# COOP4403.net
KiCad netlist of a schematic drawn in Altium Designer
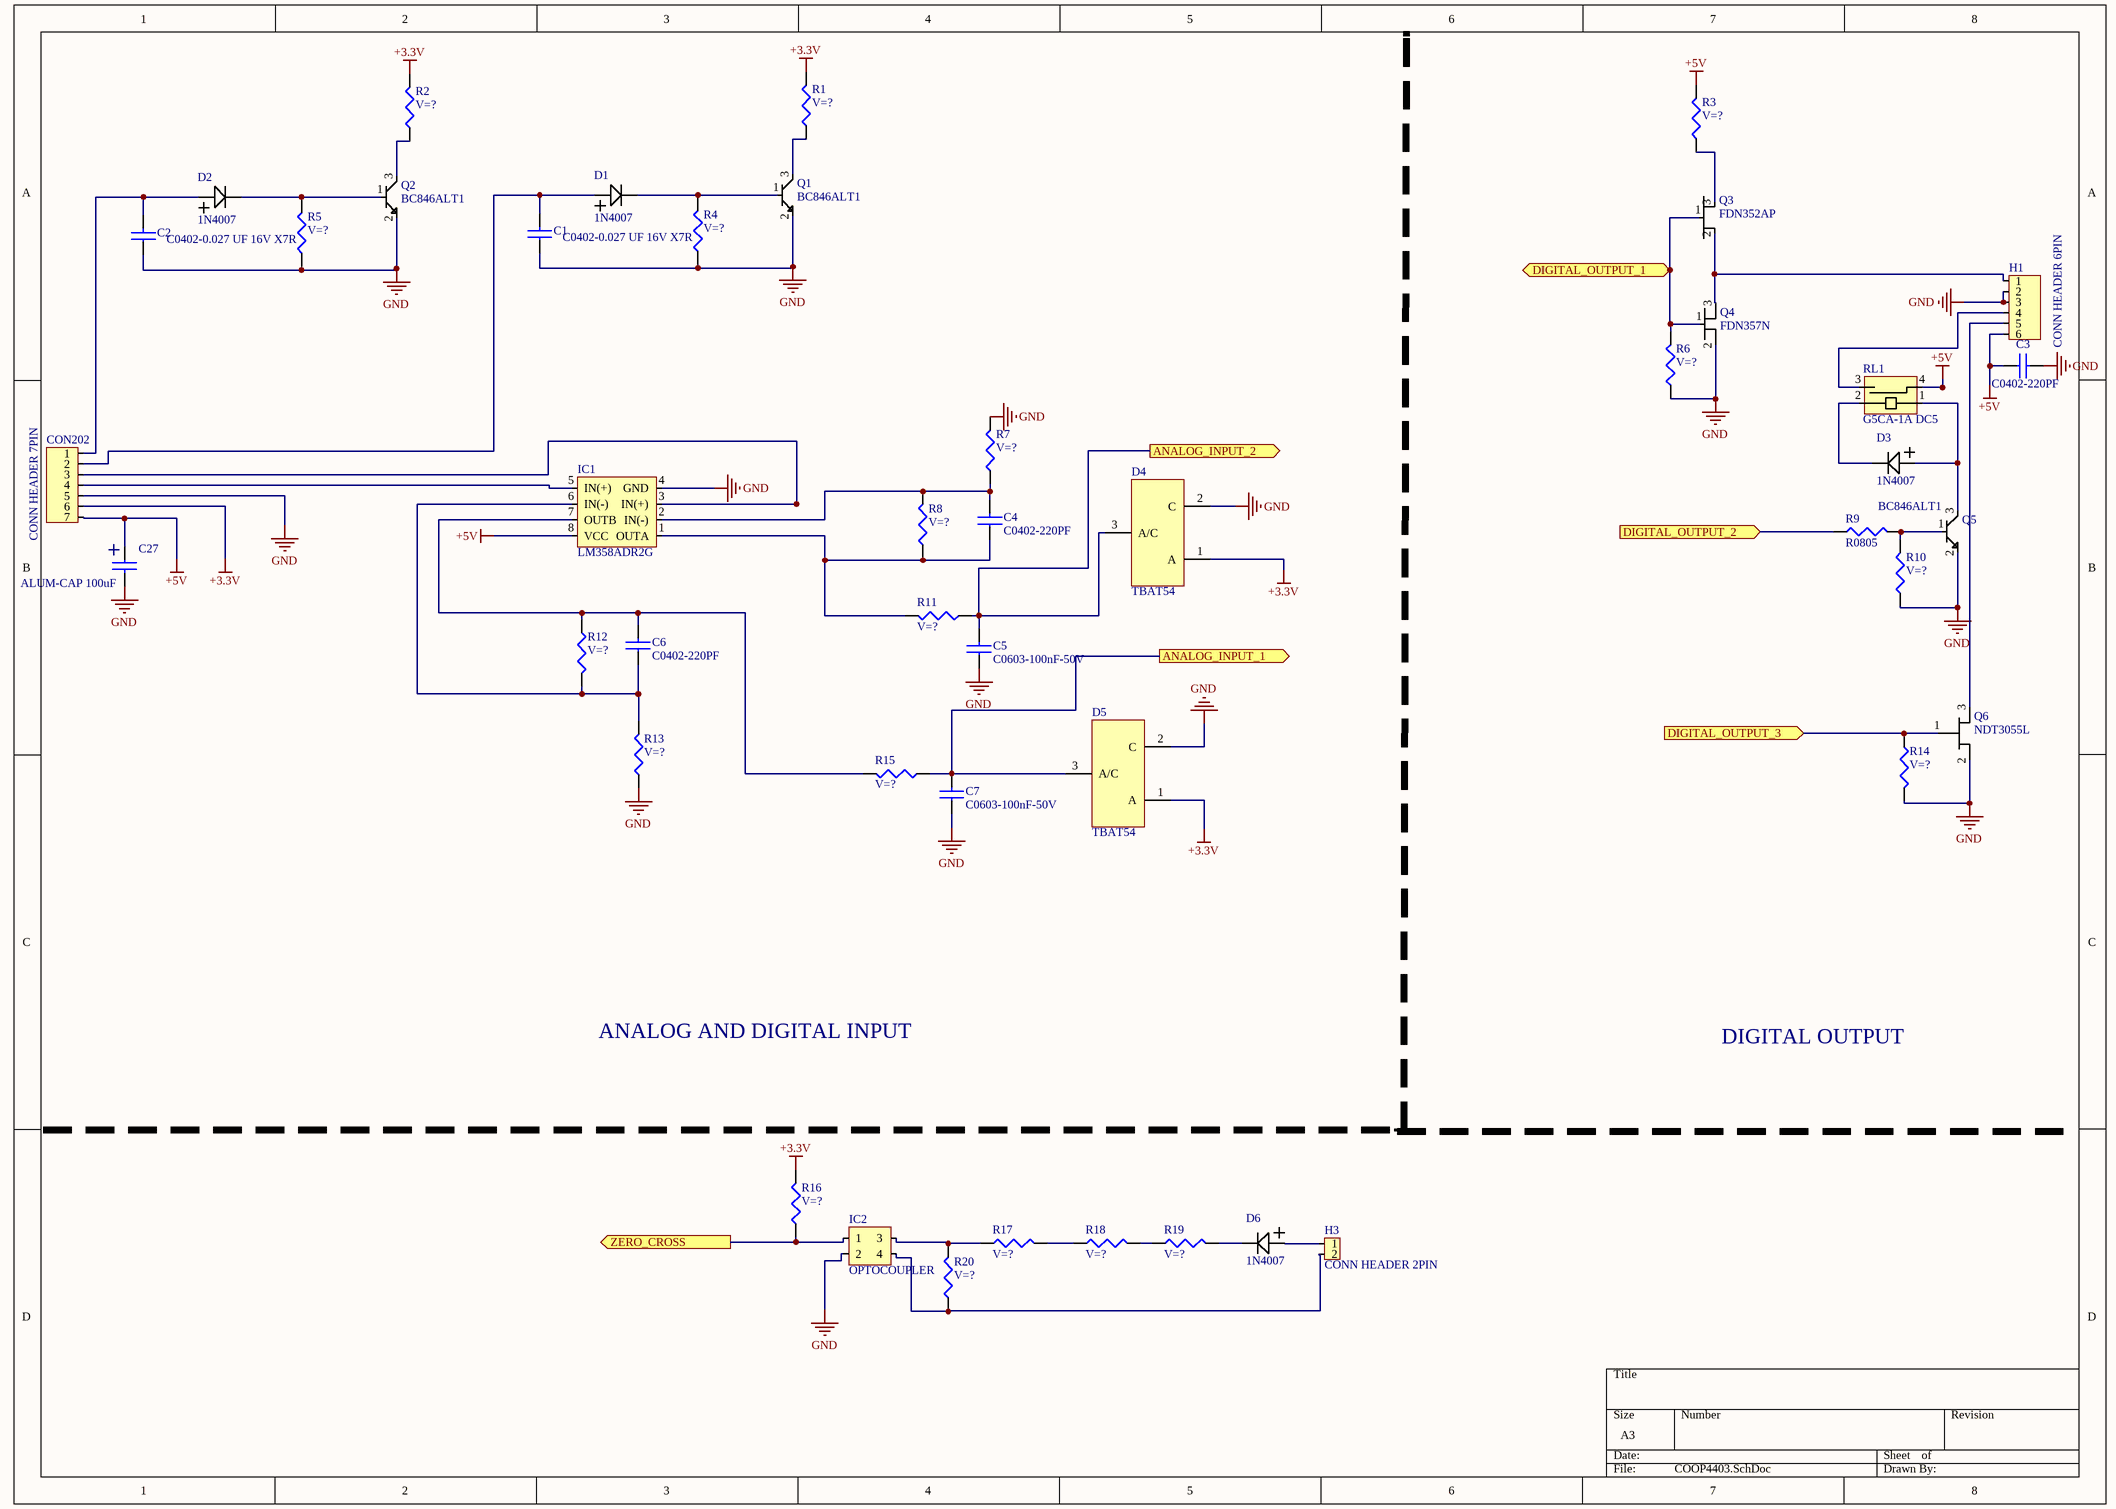
[diagram p0: COOP4403.SchDoc]

(export (version "E")
  (design (tool "Eeschema 10.0.6"))
  (components
    (comp (ref "C1")
      (value "C0402-0.027 UF 16V X7R")
      (footprint "C0402")
      (description "CAP CER 0.027 UF 16V X7R")
      (libsource (lib "COOP4403_BerkantAY") (part "C0402-0.027 UF 16V X7R"))
    )
    (comp (ref "C2")
      (value "C0402-0.027 UF 16V X7R")
      (footprint "C0402")
      (description "CAP CER 0.027 UF 16V X7R")
      (libsource (lib "COOP4403_BerkantAY") (part "C0402-0.027 UF 16V X7R"))
    )
    (comp (ref "C3")
      (value "C0402-220PF")
      (footprint "C0402")
      (description "CAP CER 220PF 50V C0G/NP0 0402")
      (libsource (lib "COOP4403_BerkantAY") (part "C0402-220PF"))
    )
    (comp (ref "C4")
      (value "C0402-220PF")
      (footprint "C0402")
      (description "CAP CER 220PF 50V C0G/NP0 0402")
      (libsource (lib "COOP4403_BerkantAY") (part "C0402-220PF"))
    )
    (comp (ref "C5")
      (value "C0603-100nF-50V")
      (footprint "C0603")
      (description "CL10B104KB8NNNC")
      (libsource (lib "COOP4403_BerkantAY") (part "C0603-100nF-50V"))
    )
    (comp (ref "C6")
      (value "C0402-220PF")
      (footprint "C0402")
      (description "CAP CER 220PF 50V C0G/NP0 0402")
      (libsource (lib "COOP4403_BerkantAY") (part "C0402-220PF"))
    )
    (comp (ref "C7")
      (value "C0603-100nF-50V")
      (footprint "C0603")
      (description "CL10B104KB8NNNC")
      (libsource (lib "COOP4403_BerkantAY") (part "C0603-100nF-50V"))
    )
    (comp (ref "C27")
      (value "ALUM-CAP 100uF")
      (footprint "ALUM-CAP")
      (description "CAP ALUM 100uF 20% 35V Radial")
      (libsource (lib "COOP4403_BerkantAY") (part "ALUM-CAP 100uF"))
    )
    (comp (ref "CON202")
      (value "CONN HEADER 7PIN")
      (footprint "CON HEADER 7PIN")
      (description "B7B-XHA")
      (libsource (lib "COOP4403_BerkantAY") (part "CONN HEADER 7PIN"))
    )
    (comp (ref "D1")
      (value "1N4007")
      (footprint "sm4007")
      (description "ONSEMI 1N4007")
      (libsource (lib "COOP4403_BerkantAY") (part "1N4007"))
    )
    (comp (ref "D2")
      (value "1N4007")
      (footprint "sm4007")
      (description "ONSEMI 1N4007")
      (libsource (lib "COOP4403_BerkantAY") (part "1N4007"))
    )
    (comp (ref "D3")
      (value "1N4007")
      (footprint "sm4007")
      (description "ONSEMI 1N4007")
      (libsource (lib "COOP4403_BerkantAY") (part "1N4007"))
    )
    (comp (ref "D4")
      (value "TBAT54")
      (footprint "SOT95P245X110-3N")
      (libsource (lib "COOP4403_BerkantAY") (part "TBAT54"))
    )
    (comp (ref "D5")
      (value "TBAT54")
      (footprint "SOT95P245X110-3N")
      (libsource (lib "COOP4403_BerkantAY") (part "TBAT54"))
    )
    (comp (ref "D6")
      (value "1N4007")
      (footprint "sm4007")
      (description "ONSEMI 1N4007")
      (libsource (lib "COOP4403_BerkantAY") (part "1N4007"))
    )
    (comp (ref "H1")
      (value "CONN HEADER 6PIN")
      (footprint "CON HEADER 6PIN")
      (description "B6B-XHA")
      (libsource (lib "COOP4403_BerkantAY") (part "CONN HEADER 6PIN"))
    )
    (comp (ref "H3")
      (value "CONN HEADER 2PIN")
      (footprint "CON HEADER 2PIN")
      (description "B2P-VHLFSN")
      (libsource (lib "COOP4403_BerkantAY") (part "CONN HEADER 2PIN"))
    )
    (comp (ref "IC1")
      (value "LM358ADR2G")
      (footprint "SOP127P700X380-8N")
      (libsource (lib "COOP4403_BerkantAY") (part "LM358ADR2G"))
    )
    (comp (ref "IC2")
      (value "OPTOCOUPLER")
      (footprint "4DIP_OPTO - duplicate")
      (libsource (lib "COOP4403_BerkantAY") (part "OPTOCOUPLER"))
    )
    (comp (ref "Q1")
      (value "BC846ALT1")
      (footprint "BC846ALT")
      (description "BJT TRANSISTOR NPN 65V 100MA")
      (libsource (lib "COOP4403_BerkantAY") (part "BC846ALT1"))
    )
    (comp (ref "Q2")
      (value "BC846ALT1")
      (footprint "BC846ALT")
      (description "BJT TRANSISTOR NPN 65V 100MA")
      (libsource (lib "COOP4403_BerkantAY") (part "BC846ALT1"))
    )
    (comp (ref "Q3")
      (value "FDN352AP")
      (footprint "FDN")
      (description "MOSFET SINGLE PCH TRENCH")
      (libsource (lib "COOP4403_BerkantAY") (part "FDN352AP"))
    )
    (comp (ref "Q4")
      (value "FDN357N")
      (footprint "FDN")
      (description "N CHANNEL LOGIC LEVEL ENGANCEMENT MODE FIELD EFFECT TRANSISTOR")
      (libsource (lib "COOP4403_BerkantAY") (part "FDN357N"))
    )
    (comp (ref "Q5")
      (value "BC846ALT1")
      (footprint "BC846ALT")
      (description "BJT TRANSISTOR NPN 65V 100MA")
      (libsource (lib "COOP4403_BerkantAY") (part "BC846ALT1"))
    )
    (comp (ref "Q6")
      (value "NDT3055L")
      (footprint "realndt")
      (description "N CHANNEL LOGIC LEVEL ENHANCEMENET MODE FIELD EFFECT TRANSISTOR")
      (libsource (lib "COOP4403_BerkantAY") (part "NDT3055L"))
    )
    (comp (ref "R1")
      (value "V=?")
      (footprint "r0402")
      (description "RESISTOR")
      (libsource (lib "COOP4403_BerkantAY") (part "R0402"))
    )
    (comp (ref "R2")
      (value "V=?")
      (footprint "r0402")
      (description "RESISTOR")
      (libsource (lib "COOP4403_BerkantAY") (part "R0402"))
    )
    (comp (ref "R3")
      (value "V=?")
      (footprint "r0402")
      (description "RESISTOR")
      (libsource (lib "COOP4403_BerkantAY") (part "R0402"))
    )
    (comp (ref "R4")
      (value "V=?")
      (footprint "R603")
      (description "CRCW06034R70FNEA")
      (libsource (lib "COOP4403_BerkantAY") (part "R0603"))
    )
    (comp (ref "R5")
      (value "V=?")
      (footprint "R603")
      (description "CRCW06034R70FNEA")
      (libsource (lib "COOP4403_BerkantAY") (part "R0603"))
    )
    (comp (ref "R6")
      (value "V=?")
      (footprint "R603")
      (description "CRCW06034R70FNEA")
      (libsource (lib "COOP4403_BerkantAY") (part "R0603"))
    )
    (comp (ref "R7")
      (value "V=?")
      (footprint "r0402")
      (description "RESISTOR")
      (libsource (lib "COOP4403_BerkantAY") (part "R0402"))
    )
    (comp (ref "R8")
      (value "V=?")
      (footprint "r0402")
      (description "RESISTOR")
      (libsource (lib "COOP4403_BerkantAY") (part "R0402"))
    )
    (comp (ref "R9")
      (value "R0805")
      (footprint "R0805")
      (libsource (lib "COOP4403_BerkantAY") (part "R0805"))
    )
    (comp (ref "R10")
      (value "V=?")
      (footprint "r0402")
      (description "RESISTOR")
      (libsource (lib "COOP4403_BerkantAY") (part "R0402"))
    )
    (comp (ref "R11")
      (value "V=?")
      (footprint "r0402")
      (description "RESISTOR")
      (libsource (lib "COOP4403_BerkantAY") (part "R0402"))
    )
    (comp (ref "R12")
      (value "V=?")
      (footprint "r0402")
      (description "RESISTOR")
      (libsource (lib "COOP4403_BerkantAY") (part "R0402"))
    )
    (comp (ref "R13")
      (value "V=?")
      (footprint "r0402")
      (description "RESISTOR")
      (libsource (lib "COOP4403_BerkantAY") (part "R0402"))
    )
    (comp (ref "R14")
      (value "V=?")
      (footprint "R603")
      (description "CRCW06034R70FNEA")
      (libsource (lib "COOP4403_BerkantAY") (part "R0603"))
    )
    (comp (ref "R15")
      (value "V=?")
      (footprint "r0402")
      (description "RESISTOR")
      (libsource (lib "COOP4403_BerkantAY") (part "R0402"))
    )
    (comp (ref "R16")
      (value "V=?")
      (footprint "r0402")
      (description "RESISTOR")
      (libsource (lib "COOP4403_BerkantAY") (part "R0402"))
    )
    (comp (ref "R17")
      (value "V=?")
      (footprint "R1206")
      (description "ERJ-8ENF10R0V")
      (libsource (lib "COOP4403_BerkantAY") (part "R1206"))
    )
    (comp (ref "R18")
      (value "V=?")
      (footprint "R1206")
      (description "ERJ-8ENF10R0V")
      (libsource (lib "COOP4403_BerkantAY") (part "R1206"))
    )
    (comp (ref "R19")
      (value "V=?")
      (footprint "R1206")
      (description "ERJ-8ENF10R0V")
      (libsource (lib "COOP4403_BerkantAY") (part "R1206"))
    )
    (comp (ref "R20")
      (value "V=?")
      (footprint "R603")
      (description "CRCW06034R70FNEA")
      (libsource (lib "COOP4403_BerkantAY") (part "R0603"))
    )
    (comp (ref "RL1")
      (value "G5CA-1A DC5")
      (footprint "RELAY OMRON")
      (description "RELAY GEN PURPOSES SPST 10A 5V")
      (libsource (lib "COOP4403_BerkantAY") (part "G5CA-1A DC5"))
    )
  )
  (nets
    (net (code "1") (name "+3.3V") (class "Default")
      (node (ref "CON202") (pin "6") (pinfunction "6_6") (pintype "passive"))
      (node (ref "D4") (pin "1") (pinfunction "A_1") (pintype "passive"))
      (node (ref "D5") (pin "1") (pinfunction "A_1") (pintype "passive"))
      (node (ref "R1") (pin "2") (pinfunction "2_2") (pintype "passive"))
      (node (ref "R16") (pin "2") (pinfunction "2_2") (pintype "passive"))
      (node (ref "R2") (pin "2") (pinfunction "2_2") (pintype "passive"))
    )
    (net (code "2") (name "+5V") (class "Default")
      (node (ref "C27") (pin "1") (pinfunction "1_1") (pintype "passive"))
      (node (ref "C3") (pin "1") (pinfunction "1_1") (pintype "passive"))
      (node (ref "CON202") (pin "7") (pinfunction "7_7") (pintype "passive"))
      (node (ref "H1") (pin "6") (pinfunction "6_6") (pintype "passive"))
      (node (ref "IC1") (pin "8") (pinfunction "VCC_8") (pintype "passive"))
      (node (ref "R3") (pin "2") (pinfunction "2_2") (pintype "passive"))
      (node (ref "RL1") (pin "4") (pinfunction "4_4") (pintype "passive"))
    )
    (net (code "3") (name "/ANALOG_INPUT_1") (class "Default")
      (node (ref "C7") (pin "2") (pinfunction "2_2") (pintype "passive"))
      (node (ref "D5") (pin "3") (pinfunction "A/C_3") (pintype "passive"))
      (node (ref "R15") (pin "1") (pinfunction "1_1") (pintype "passive"))
    )
    (net (code "4") (name "/ANALOG_INPUT_2") (class "Default")
      (node (ref "C5") (pin "2") (pinfunction "2_2") (pintype "passive"))
      (node (ref "D4") (pin "3") (pinfunction "A/C_3") (pintype "passive"))
      (node (ref "R11") (pin "1") (pinfunction "1_1") (pintype "passive"))
    )
    (net (code "5") (name "/DIGITAL_OUTPUT_1") (class "Default")
      (node (ref "Q3") (pin "1") (pinfunction "1_1") (pintype "passive"))
      (node (ref "Q4") (pin "1") (pinfunction "1_1") (pintype "passive"))
      (node (ref "R6") (pin "2") (pinfunction "2_2") (pintype "passive"))
    )
    (net (code "6") (name "/DIGITAL_OUTPUT_2") (class "Default")
      (node (ref "R9") (pin "1") (pinfunction "1_1") (pintype "passive"))
    )
    (net (code "7") (name "/DIGITAL_OUTPUT_3") (class "Default")
      (node (ref "Q6") (pin "1") (pinfunction "1_1") (pintype "passive"))
      (node (ref "R14") (pin "1") (pinfunction "1_1") (pintype "passive"))
    )
    (net (code "8") (name "/ZERO_CROSS") (class "Default")
      (node (ref "IC2") (pin "1") (pinfunction "1_1") (pintype "passive"))
      (node (ref "R16") (pin "1") (pinfunction "1_1") (pintype "passive"))
    )
    (net (code "9") (name "GND") (class "Default")
      (node (ref "C1") (pin "1") (pinfunction "1_1") (pintype "passive"))
      (node (ref "C2") (pin "1") (pinfunction "1_1") (pintype "passive"))
      (node (ref "C27") (pin "2") (pinfunction "2_2") (pintype "passive"))
      (node (ref "C3") (pin "2") (pinfunction "2_2") (pintype "passive"))
      (node (ref "C5") (pin "1") (pinfunction "1_1") (pintype "passive"))
      (node (ref "C7") (pin "1") (pinfunction "1_1") (pintype "passive"))
      (node (ref "CON202") (pin "5") (pinfunction "5_5") (pintype "passive"))
      (node (ref "D4") (pin "2") (pinfunction "C_2") (pintype "passive"))
      (node (ref "D5") (pin "2") (pinfunction "C_2") (pintype "passive"))
      (node (ref "H1") (pin "2") (pinfunction "2_2") (pintype "passive"))
      (node (ref "H1") (pin "3") (pinfunction "3_3") (pintype "passive"))
      (node (ref "IC1") (pin "4") (pinfunction "GND_4") (pintype "passive"))
      (node (ref "IC2") (pin "2") (pinfunction "2_2") (pintype "passive"))
      (node (ref "Q1") (pin "2") (pinfunction "2_2") (pintype "passive"))
      (node (ref "Q2") (pin "2") (pinfunction "2_2") (pintype "passive"))
      (node (ref "Q4") (pin "2") (pinfunction "2_2") (pintype "passive"))
      (node (ref "Q5") (pin "2") (pinfunction "2_2") (pintype "passive"))
      (node (ref "Q6") (pin "2") (pinfunction "2_2") (pintype "passive"))
      (node (ref "R10") (pin "1") (pinfunction "1_1") (pintype "passive"))
      (node (ref "R13") (pin "1") (pinfunction "1_1") (pintype "passive"))
      (node (ref "R14") (pin "2") (pinfunction "2_2") (pintype "passive"))
      (node (ref "R4") (pin "1") (pinfunction "1_1") (pintype "passive"))
      (node (ref "R5") (pin "1") (pinfunction "1_1") (pintype "passive"))
      (node (ref "R6") (pin "1") (pinfunction "1_1") (pintype "passive"))
      (node (ref "R7") (pin "2") (pinfunction "2_2") (pintype "passive"))
    )
    (net (code "10") (name "Net-(C1-Pad2)") (class "Default")
      (node (ref "C1") (pin "2") (pinfunction "2_2") (pintype "passive"))
      (node (ref "CON202") (pin "2") (pinfunction "2_2") (pintype "passive"))
      (node (ref "D1") (pin "1") (pinfunction "1_1") (pintype "passive"))
    )
    (net (code "11") (name "Net-(C2-Pad2)") (class "Default")
      (node (ref "C2") (pin "2") (pinfunction "2_2") (pintype "passive"))
      (node (ref "CON202") (pin "1") (pinfunction "1_1") (pintype "passive"))
      (node (ref "D2") (pin "1") (pinfunction "1_1") (pintype "passive"))
    )
    (net (code "12") (name "Net-(C4-Pad2)") (class "Default")
      (node (ref "C4") (pin "2") (pinfunction "2_2") (pintype "passive"))
      (node (ref "IC1") (pin "2") (pinfunction "IN(-)_2") (pintype "passive"))
      (node (ref "R7") (pin "1") (pinfunction "1_1") (pintype "passive"))
      (node (ref "R8") (pin "2") (pinfunction "2_2") (pintype "passive"))
    )
    (net (code "13") (name "Net-(C6-Pad1)") (class "Default")
      (node (ref "C6") (pin "1") (pinfunction "1_1") (pintype "passive"))
      (node (ref "IC1") (pin "6") (pinfunction "IN(-)_6") (pintype "passive"))
      (node (ref "R12") (pin "2") (pinfunction "2_2") (pintype "passive"))
      (node (ref "R13") (pin "2") (pinfunction "2_2") (pintype "passive"))
    )
    (net (code "14") (name "Net-(CON202-Pad3)") (class "Default")
      (node (ref "CON202") (pin "3") (pinfunction "3_3") (pintype "passive"))
      (node (ref "IC1") (pin "3") (pinfunction "IN(+)_3") (pintype "passive"))
    )
    (net (code "15") (name "Net-(CON202-Pad4)") (class "Default")
      (node (ref "CON202") (pin "4") (pinfunction "4_4") (pintype "passive"))
      (node (ref "IC1") (pin "5") (pinfunction "IN(+)_5") (pintype "passive"))
    )
    (net (code "16") (name "Net-(D1-Pad2)") (class "Default")
      (node (ref "D1") (pin "2") (pintype "passive"))
      (node (ref "Q1") (pin "1") (pinfunction "1_1") (pintype "passive"))
      (node (ref "R4") (pin "2") (pinfunction "2_2") (pintype "passive"))
    )
    (net (code "17") (name "Net-(D2-Pad2)") (class "Default")
      (node (ref "D2") (pin "2") (pintype "passive"))
      (node (ref "Q2") (pin "1") (pinfunction "1_1") (pintype "passive"))
      (node (ref "R5") (pin "2") (pinfunction "2_2") (pintype "passive"))
    )
    (net (code "18") (name "Net-(D3-Pad1)") (class "Default")
      (node (ref "D3") (pin "1") (pinfunction "1_1") (pintype "passive"))
      (node (ref "Q5") (pin "3") (pinfunction "3_3") (pintype "passive"))
      (node (ref "RL1") (pin "1") (pinfunction "1_1") (pintype "passive"))
    )
    (net (code "19") (name "Net-(D3-Pad2)") (class "Default")
      (node (ref "D3") (pin "2") (pintype "passive"))
      (node (ref "RL1") (pin "2") (pinfunction "2_2") (pintype "passive"))
    )
    (net (code "20") (name "Net-(D6-Pad1)") (class "Default")
      (node (ref "D6") (pin "1") (pinfunction "1_1") (pintype "passive"))
      (node (ref "H3") (pin "1") (pinfunction "1_1") (pintype "passive"))
    )
    (net (code "21") (name "Net-(D6-Pad2)") (class "Default")
      (node (ref "D6") (pin "2") (pintype "passive"))
      (node (ref "R19") (pin "2") (pinfunction "2_2") (pintype "passive"))
    )
    (net (code "22") (name "Net-(H1-Pad1)") (class "Default")
      (node (ref "H1") (pin "1") (pinfunction "1_1") (pintype "passive"))
      (node (ref "Q3") (pin "2") (pinfunction "2_2") (pintype "passive"))
      (node (ref "Q4") (pin "3") (pinfunction "3_3") (pintype "passive"))
    )
    (net (code "23") (name "Net-(H1-Pad4)") (class "Default")
      (node (ref "H1") (pin "4") (pinfunction "4_4") (pintype "passive"))
      (node (ref "RL1") (pin "3") (pinfunction "3_3") (pintype "passive"))
    )
    (net (code "24") (name "Net-(H1-Pad5)") (class "Default")
      (node (ref "H1") (pin "5") (pinfunction "5_5") (pintype "passive"))
      (node (ref "Q6") (pin "3") (pinfunction "3_3") (pintype "passive"))
    )
    (net (code "25") (name "Net-(H3-Pad2)") (class "Default")
      (node (ref "H3") (pin "2") (pinfunction "2_2") (pintype "passive"))
      (node (ref "IC2") (pin "4") (pinfunction "4_4") (pintype "passive"))
      (node (ref "R20") (pin "1") (pinfunction "1_1") (pintype "passive"))
    )
    (net (code "26") (name "Net-(IC1-OUTA)") (class "Default")
      (node (ref "C4") (pin "1") (pinfunction "1_1") (pintype "passive"))
      (node (ref "IC1") (pin "1") (pinfunction "OUTA_1") (pintype "passive"))
      (node (ref "R11") (pin "2") (pinfunction "2_2") (pintype "passive"))
      (node (ref "R8") (pin "1") (pinfunction "1_1") (pintype "passive"))
    )
    (net (code "27") (name "Net-(IC1-OUTB)") (class "Default")
      (node (ref "C6") (pin "2") (pinfunction "2_2") (pintype "passive"))
      (node (ref "IC1") (pin "7") (pinfunction "OUTB_7") (pintype "passive"))
      (node (ref "R12") (pin "1") (pinfunction "1_1") (pintype "passive"))
      (node (ref "R15") (pin "2") (pinfunction "2_2") (pintype "passive"))
    )
    (net (code "28") (name "Net-(IC2-Pad3)") (class "Default")
      (node (ref "IC2") (pin "3") (pinfunction "3_3") (pintype "passive"))
      (node (ref "R17") (pin "1") (pinfunction "1_1") (pintype "passive"))
      (node (ref "R20") (pin "2") (pinfunction "2_2") (pintype "passive"))
    )
    (net (code "29") (name "Net-(Q1-Pad3)") (class "Default")
      (node (ref "Q1") (pin "3") (pinfunction "3_3") (pintype "passive"))
      (node (ref "R1") (pin "1") (pinfunction "1_1") (pintype "passive"))
    )
    (net (code "30") (name "Net-(Q2-Pad3)") (class "Default")
      (node (ref "Q2") (pin "3") (pinfunction "3_3") (pintype "passive"))
      (node (ref "R2") (pin "1") (pinfunction "1_1") (pintype "passive"))
    )
    (net (code "31") (name "Net-(Q3-Pad3)") (class "Default")
      (node (ref "Q3") (pin "3") (pinfunction "3_3") (pintype "passive"))
      (node (ref "R3") (pin "1") (pinfunction "1_1") (pintype "passive"))
    )
    (net (code "32") (name "Net-(Q5-Pad1)") (class "Default")
      (node (ref "Q5") (pin "1") (pinfunction "1_1") (pintype "passive"))
      (node (ref "R10") (pin "2") (pinfunction "2_2") (pintype "passive"))
      (node (ref "R9") (pin "2") (pinfunction "2_2") (pintype "passive"))
    )
    (net (code "33") (name "Net-(R17-Pad2)") (class "Default")
      (node (ref "R17") (pin "2") (pinfunction "2_2") (pintype "passive"))
      (node (ref "R18") (pin "1") (pinfunction "1_1") (pintype "passive"))
    )
    (net (code "34") (name "Net-(R18-Pad2)") (class "Default")
      (node (ref "R18") (pin "2") (pinfunction "2_2") (pintype "passive"))
      (node (ref "R19") (pin "1") (pinfunction "1_1") (pintype "passive"))
    )
  )
)
